# SCH_jiji_2021-11-03.net
KiCad netlist of a schematic drawn in EasyEDA
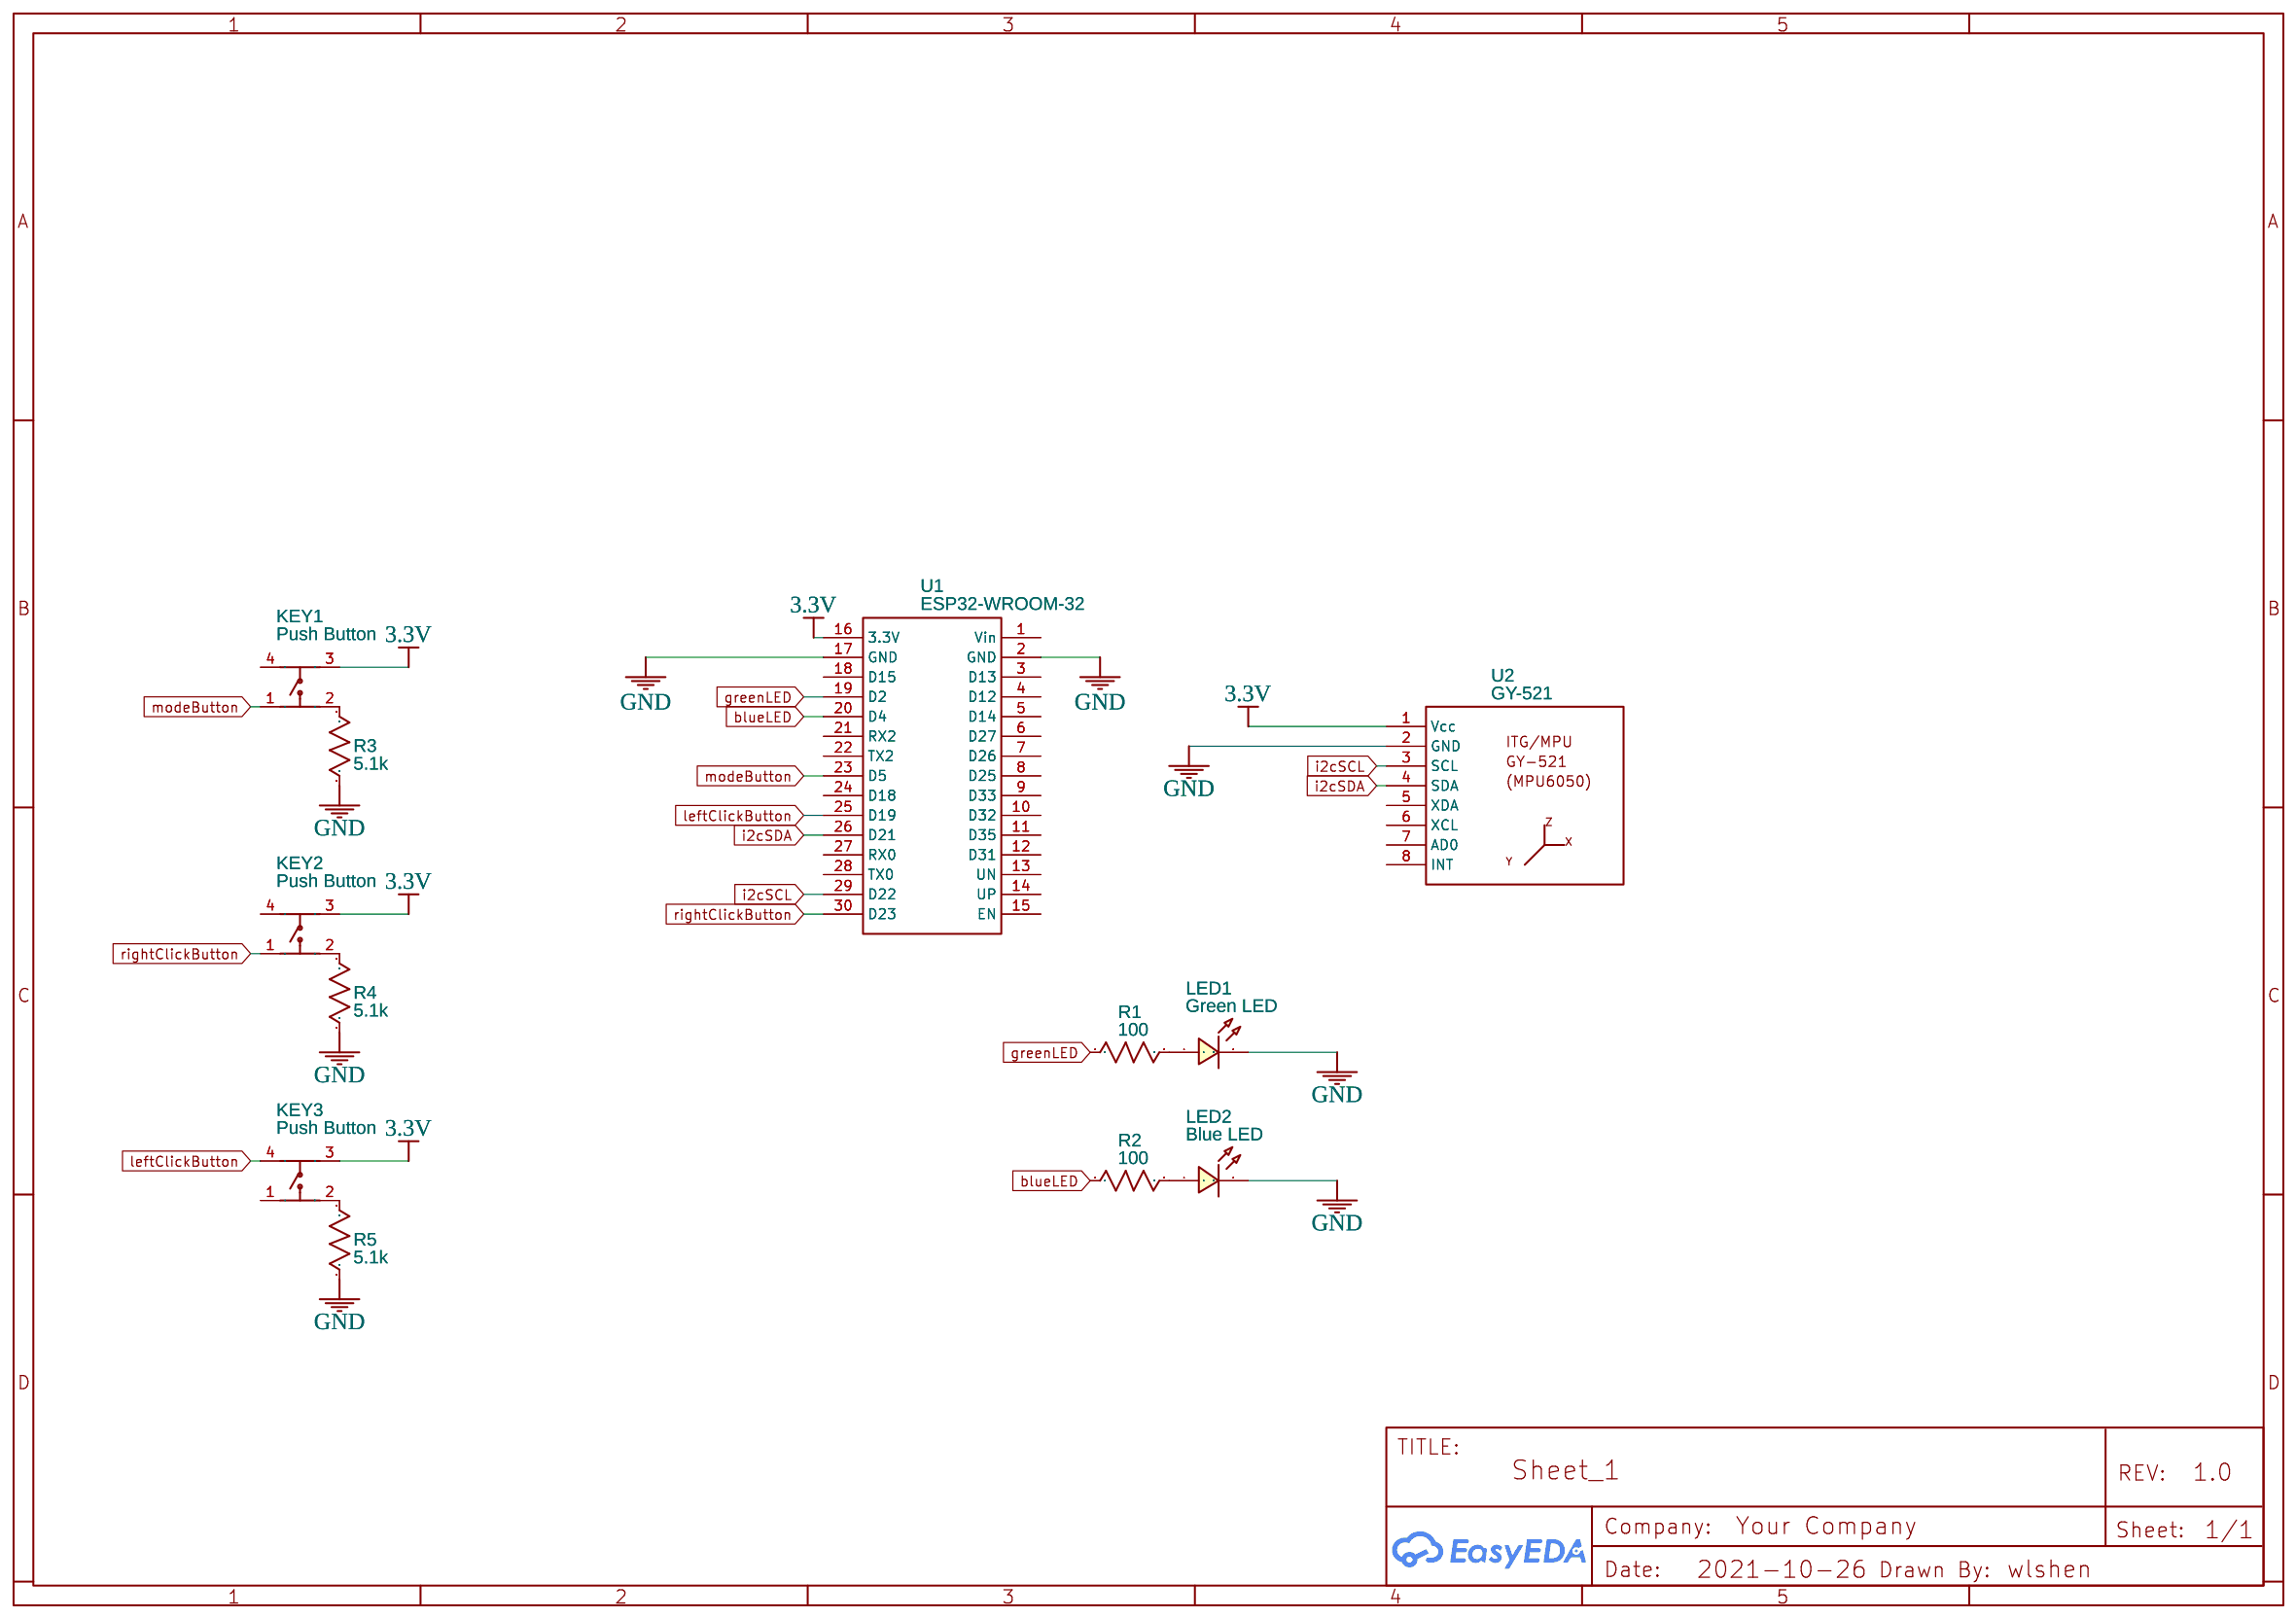
[diagram p0: schematic sheet]

(export (version "E")
  (design (tool "Eeschema 10.0.6"))
  (components
    (comp (ref "KEY1")
      (value "Push Button")
      (fields
        (field (name "BOM_Manufacturer Part") "button6*6*8")
        (field (name "BOM_Supplier Part") "C59982")
      )
      (libsource (lib "") (part "button6*6*8"))
    )
    (comp (ref "KEY2")
      (value "Push Button")
      (fields
        (field (name "BOM_Manufacturer Part") "button6*6*8")
        (field (name "BOM_Supplier Part") "C59982")
      )
      (libsource (lib "") (part "button6*6*8"))
    )
    (comp (ref "KEY3")
      (value "Push Button")
      (fields
        (field (name "BOM_Manufacturer Part") "button6*6*8")
        (field (name "BOM_Supplier Part") "C59982")
      )
      (libsource (lib "") (part "button6*6*8"))
    )
    (comp (ref "LED1")
      (value "Green LED")
      (fields
        (field (name "BOM_Manufacturer Part") "19-217/R6C-AL1M2VY/3T")
        (field (name "BOM_Supplier Part") "C72044")
      )
      (libsource (lib "") (part "LED-0603_R"))
    )
    (comp (ref "LED2")
      (value "Blue LED")
      (fields
        (field (name "BOM_Manufacturer Part") "19-217/R6C-AL1M2VY/3T")
        (field (name "BOM_Supplier Part") "C72044")
      )
      (libsource (lib "") (part "LED-0603_R"))
    )
    (comp (ref "R1") (value "100") (libsource (lib "") (part "R_0201_US")))
    (comp (ref "R2") (value "100") (libsource (lib "") (part "R_0201_US")))
    (comp (ref "R3") (value "5.1k") (libsource (lib "") (part "R_0201_US_1")))
    (comp (ref "R4") (value "5.1k") (libsource (lib "") (part "R_0201_US_1")))
    (comp (ref "R5") (value "5.1k") (libsource (lib "") (part "R_0201_US_1")))
    (comp (ref "U1") (value "ESP32-WROOM-32") (libsource (lib "") (part "ESP32-WROOM-32")))
    (comp (ref "U2") (value "GY-521") (libsource (lib "") (part "GY-521")))
  )
  (nets
    (net (code "1") (name "3.3V") (class "Default")
      (node (ref "KEY1") (pin "3") (pinfunction "3_3") (pintype "unspecified"))
      (node (ref "KEY2") (pin "3") (pinfunction "3_3") (pintype "unspecified"))
      (node (ref "KEY3") (pin "3") (pinfunction "3_3") (pintype "unspecified"))
      (node (ref "U1") (pin "16") (pinfunction "3.3V_16") (pintype "unspecified"))
      (node (ref "U2") (pin "1") (pinfunction "Vcc_1") (pintype "unspecified"))
    )
    (net (code "2") (name "GND") (class "Default")
      (node (ref "LED1") (pin "2") (pinfunction "2_2") (pintype "unspecified"))
      (node (ref "LED2") (pin "2") (pinfunction "2_2") (pintype "unspecified"))
      (node (ref "R3") (pin "1") (pinfunction "1_1") (pintype "unspecified"))
      (node (ref "R4") (pin "1") (pinfunction "1_1") (pintype "unspecified"))
      (node (ref "R5") (pin "1") (pinfunction "1_1") (pintype "unspecified"))
      (node (ref "U1") (pin "17") (pinfunction "GND_17") (pintype "unspecified"))
      (node (ref "U1") (pin "2") (pinfunction "GND_2") (pintype "unspecified"))
      (node (ref "U2") (pin "2") (pinfunction "GND_2") (pintype "unspecified"))
    )
    (net (code "3") (name "Net-(KEY1-Pad2)") (class "Default")
      (node (ref "KEY1") (pin "2") (pinfunction "2_2") (pintype "unspecified"))
      (node (ref "R3") (pin "2") (pinfunction "2_2") (pintype "unspecified"))
    )
    (net (code "4") (name "Net-(KEY2-Pad2)") (class "Default")
      (node (ref "KEY2") (pin "2") (pinfunction "2_2") (pintype "unspecified"))
      (node (ref "R4") (pin "2") (pinfunction "2_2") (pintype "unspecified"))
    )
    (net (code "5") (name "Net-(KEY3-Pad2)") (class "Default")
      (node (ref "KEY3") (pin "2") (pinfunction "2_2") (pintype "unspecified"))
      (node (ref "R5") (pin "2") (pinfunction "2_2") (pintype "unspecified"))
    )
    (net (code "6") (name "Net-(LED1-Pad1)") (class "Default")
      (node (ref "LED1") (pin "1") (pinfunction "1_1") (pintype "unspecified"))
      (node (ref "R1") (pin "2") (pinfunction "2_2") (pintype "unspecified"))
    )
    (net (code "7") (name "Net-(LED2-Pad1)") (class "Default")
      (node (ref "LED2") (pin "1") (pinfunction "1_1") (pintype "unspecified"))
      (node (ref "R2") (pin "2") (pinfunction "2_2") (pintype "unspecified"))
    )
    (net (code "8") (name "blueLED") (class "Default")
      (node (ref "R2") (pin "1") (pinfunction "1_1") (pintype "unspecified"))
      (node (ref "U1") (pin "20") (pinfunction "D4_20") (pintype "unspecified"))
    )
    (net (code "9") (name "greenLED") (class "Default")
      (node (ref "R1") (pin "1") (pinfunction "1_1") (pintype "unspecified"))
      (node (ref "U1") (pin "19") (pinfunction "D2_19") (pintype "unspecified"))
    )
    (net (code "10") (name "i2cSCL") (class "Default")
      (node (ref "U1") (pin "29") (pinfunction "D22_29") (pintype "unspecified"))
      (node (ref "U2") (pin "3") (pinfunction "SCL_3") (pintype "unspecified"))
    )
    (net (code "11") (name "i2cSDA") (class "Default")
      (node (ref "U1") (pin "26") (pinfunction "D21_26") (pintype "unspecified"))
      (node (ref "U2") (pin "4") (pinfunction "SDA_4") (pintype "unspecified"))
    )
    (net (code "12") (name "leftClickButton") (class "Default")
      (node (ref "KEY3") (pin "4") (pinfunction "4_4") (pintype "unspecified"))
      (node (ref "U1") (pin "25") (pinfunction "D19_25") (pintype "unspecified"))
    )
    (net (code "13") (name "modeButton") (class "Default")
      (node (ref "KEY1") (pin "1") (pinfunction "1_1") (pintype "unspecified"))
      (node (ref "U1") (pin "23") (pinfunction "D5_23") (pintype "unspecified"))
    )
    (net (code "14") (name "rightClickButton") (class "Default")
      (node (ref "KEY2") (pin "1") (pinfunction "1_1") (pintype "unspecified"))
      (node (ref "U1") (pin "30") (pinfunction "D23_30") (pintype "unspecified"))
    )
    (net (code "15") (name "unconnected-(KEY1-Pad4)") (class "Default")
      (node (ref "KEY1") (pin "4") (pinfunction "4_4") (pintype "unspecified"))
    )
    (net (code "16") (name "unconnected-(KEY2-Pad4)") (class "Default")
      (node (ref "KEY2") (pin "4") (pinfunction "4_4") (pintype "unspecified"))
    )
    (net (code "17") (name "unconnected-(KEY3-Pad1)") (class "Default")
      (node (ref "KEY3") (pin "1") (pinfunction "1_1") (pintype "unspecified"))
    )
    (net (code "18") (name "unconnected-(U1-D12-Pad4)") (class "Default")
      (node (ref "U1") (pin "4") (pinfunction "D12_4") (pintype "unspecified"))
    )
    (net (code "19") (name "unconnected-(U1-D13-Pad3)") (class "Default")
      (node (ref "U1") (pin "3") (pinfunction "D13_3") (pintype "unspecified"))
    )
    (net (code "20") (name "unconnected-(U1-D14-Pad5)") (class "Default")
      (node (ref "U1") (pin "5") (pinfunction "D14_5") (pintype "unspecified"))
    )
    (net (code "21") (name "unconnected-(U1-D15-Pad18)") (class "Default")
      (node (ref "U1") (pin "18") (pinfunction "D15_18") (pintype "unspecified"))
    )
    (net (code "22") (name "unconnected-(U1-D18-Pad24)") (class "Default")
      (node (ref "U1") (pin "24") (pinfunction "D18_24") (pintype "unspecified"))
    )
    (net (code "23") (name "unconnected-(U1-D25-Pad8)") (class "Default")
      (node (ref "U1") (pin "8") (pinfunction "D25_8") (pintype "unspecified"))
    )
    (net (code "24") (name "unconnected-(U1-D26-Pad7)") (class "Default")
      (node (ref "U1") (pin "7") (pinfunction "D26_7") (pintype "unspecified"))
    )
    (net (code "25") (name "unconnected-(U1-D27-Pad6)") (class "Default")
      (node (ref "U1") (pin "6") (pinfunction "D27_6") (pintype "unspecified"))
    )
    (net (code "26") (name "unconnected-(U1-D31-Pad12)") (class "Default")
      (node (ref "U1") (pin "12") (pinfunction "D31_12") (pintype "unspecified"))
    )
    (net (code "27") (name "unconnected-(U1-D32-Pad10)") (class "Default")
      (node (ref "U1") (pin "10") (pinfunction "D32_10") (pintype "unspecified"))
    )
    (net (code "28") (name "unconnected-(U1-D33-Pad9)") (class "Default")
      (node (ref "U1") (pin "9") (pinfunction "D33_9") (pintype "unspecified"))
    )
    (net (code "29") (name "unconnected-(U1-D35-Pad11)") (class "Default")
      (node (ref "U1") (pin "11") (pinfunction "D35_11") (pintype "unspecified"))
    )
    (net (code "30") (name "unconnected-(U1-EN-Pad15)") (class "Default")
      (node (ref "U1") (pin "15") (pinfunction "EN_15") (pintype "unspecified"))
    )
    (net (code "31") (name "unconnected-(U1-RX0-Pad27)") (class "Default")
      (node (ref "U1") (pin "27") (pinfunction "RX0_27") (pintype "unspecified"))
    )
    (net (code "32") (name "unconnected-(U1-RX2-Pad21)") (class "Default")
      (node (ref "U1") (pin "21") (pinfunction "RX2_21") (pintype "unspecified"))
    )
    (net (code "33") (name "unconnected-(U1-TX0-Pad28)") (class "Default")
      (node (ref "U1") (pin "28") (pinfunction "TX0_28") (pintype "unspecified"))
    )
    (net (code "34") (name "unconnected-(U1-TX2-Pad22)") (class "Default")
      (node (ref "U1") (pin "22") (pinfunction "TX2_22") (pintype "unspecified"))
    )
    (net (code "35") (name "unconnected-(U1-UN-Pad13)") (class "Default")
      (node (ref "U1") (pin "13") (pinfunction "UN_13") (pintype "unspecified"))
    )
    (net (code "36") (name "unconnected-(U1-UP-Pad14)") (class "Default")
      (node (ref "U1") (pin "14") (pinfunction "UP_14") (pintype "unspecified"))
    )
    (net (code "37") (name "unconnected-(U1-Vin-Pad1)") (class "Default")
      (node (ref "U1") (pin "1") (pinfunction "Vin_1") (pintype "unspecified"))
    )
    (net (code "38") (name "unconnected-(U2-AD0-Pad7)") (class "Default")
      (node (ref "U2") (pin "7") (pinfunction "AD0_7") (pintype "unspecified"))
    )
    (net (code "39") (name "unconnected-(U2-INT-Pad8)") (class "Default")
      (node (ref "U2") (pin "8") (pinfunction "INT_8") (pintype "unspecified"))
    )
    (net (code "40") (name "unconnected-(U2-XCL-Pad6)") (class "Default")
      (node (ref "U2") (pin "6") (pinfunction "XCL_6") (pintype "unspecified"))
    )
    (net (code "41") (name "unconnected-(U2-XDA-Pad5)") (class "Default")
      (node (ref "U2") (pin "5") (pinfunction "XDA_5") (pintype "unspecified"))
    )
  )
)
